# mux_geurts_3.net
KiCad netlist of a schematic drawn in EAGLE
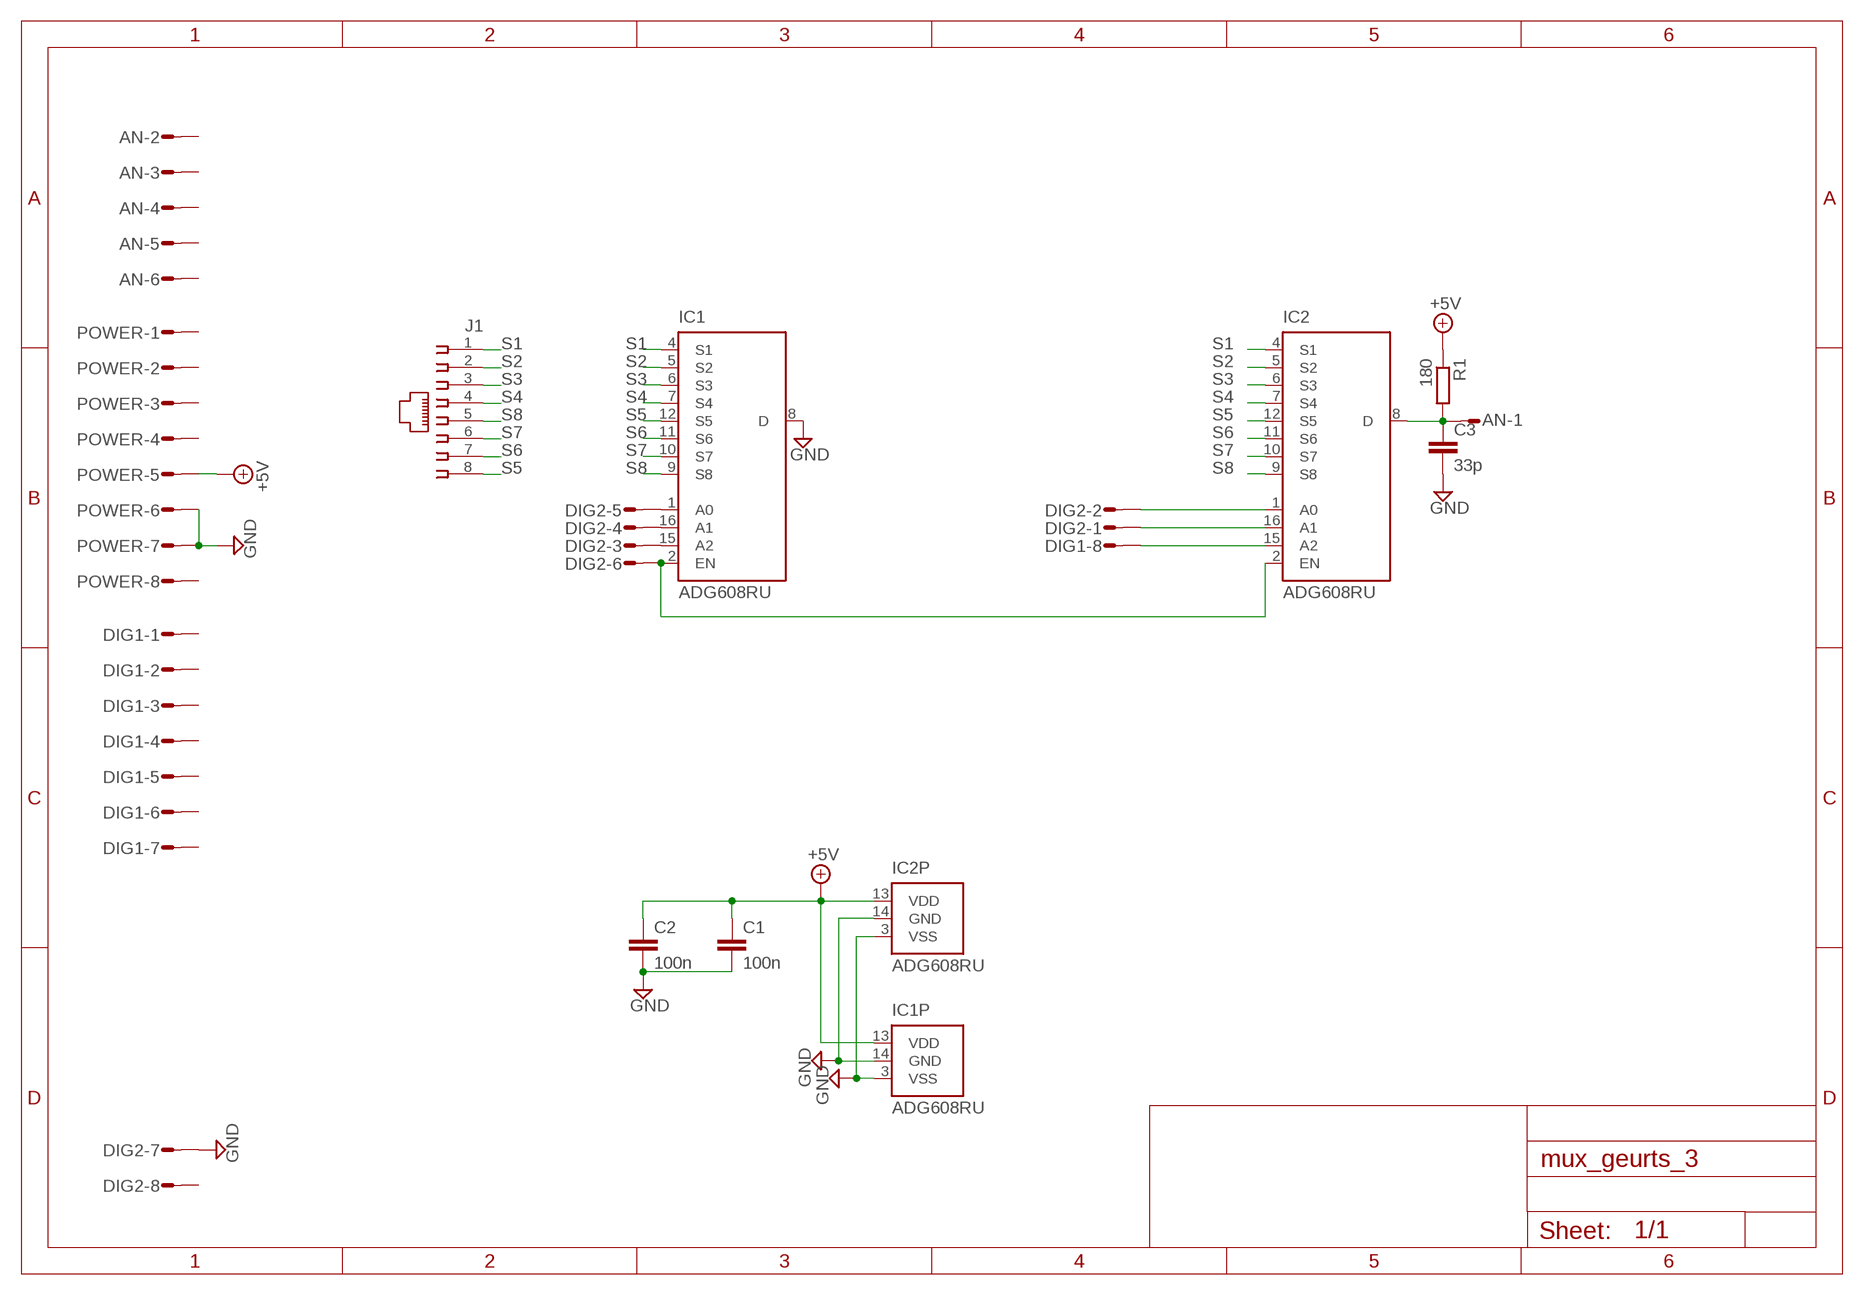
[diagram p0: schematic, sheet 1]

(export (version "E")
  (design (tool "Eeschema 10.0.6"))
  (components
    (comp (ref "AN")
      (value "M06S")
      (footprint "eagle-import:06P")
      (libsource (lib "eagle-import") (part "M06S"))
    )
    (comp (ref "C1")
      (value "100n")
      (footprint "eagle-import:C0805K")
      (libsource (lib "eagle-import") (part "C-EUC0805K"))
    )
    (comp (ref "C2")
      (value "100n")
      (footprint "eagle-import:C0805K")
      (libsource (lib "eagle-import") (part "C-EUC0805K"))
    )
    (comp (ref "C3")
      (value "33p")
      (footprint "eagle-import:C0805K")
      (libsource (lib "eagle-import") (part "C-EUC0805K"))
    )
    (comp (ref "DIG1")
      (value "M08S")
      (footprint "eagle-import:08P")
      (libsource (lib "eagle-import") (part "M08S"))
    )
    (comp (ref "DIG2")
      (value "M08S")
      (footprint "eagle-import:08P")
      (libsource (lib "eagle-import") (part "M08S"))
    )
    (comp (ref "IC1")
      (value "ADG608RU")
      (footprint "eagle-import:TSSOP16")
      (fields (field (name "MF") "ALTERA CORPORATION") (field (name "MPN") "ADG608BRU"))
      (libsource (lib "eagle-import") (part "ADG608RU"))
    )
    (comp (ref "IC2")
      (value "ADG608RU")
      (footprint "eagle-import:TSSOP16")
      (fields (field (name "MF") "ALTERA CORPORATION") (field (name "MPN") "ADG608BRU"))
      (libsource (lib "eagle-import") (part "ADG608RU"))
    )
    (comp (ref "J1")
      (value "520251-4")
      (footprint "eagle-import:520251-4")
      (libsource (lib "eagle-import") (part "520251-4"))
    )
    (comp (ref "POWER")
      (value "M08S")
      (footprint "eagle-import:08P")
      (libsource (lib "eagle-import") (part "M08S"))
    )
    (comp (ref "R1")
      (value "180")
      (footprint "eagle-import:R0805W")
      (libsource (lib "eagle-import") (part "R-EU_R0805W"))
    )
  )
  (nets
    (net (code "1") (name "+5V") (class "Default")
      (node (ref "C1") (pin "1") (pinfunction "1_1") (pintype "passive"))
      (node (ref "C2") (pin "1") (pinfunction "1_1") (pintype "passive"))
      (node (ref "IC1") (pin "13") (pinfunction "VDD_13") (pintype "power_in"))
      (node (ref "IC2") (pin "13") (pinfunction "VDD_13") (pintype "power_in"))
      (node (ref "POWER") (pin "5") (pinfunction "S_5") (pintype "passive"))
      (node (ref "R1") (pin "1") (pinfunction "1_1") (pintype "passive"))
    )
    (net (code "2") (name "/S1") (class "Default")
      (node (ref "IC1") (pin "4") (pinfunction "S1_4") (pintype "bidirectional"))
      (node (ref "IC2") (pin "4") (pinfunction "S1_4") (pintype "bidirectional"))
      (node (ref "J1") (pin "1") (pinfunction "1_1") (pintype "passive"))
    )
    (net (code "3") (name "/S2") (class "Default")
      (node (ref "IC1") (pin "5") (pinfunction "S2_5") (pintype "bidirectional"))
      (node (ref "IC2") (pin "5") (pinfunction "S2_5") (pintype "bidirectional"))
      (node (ref "J1") (pin "2") (pinfunction "2_2") (pintype "passive"))
    )
    (net (code "4") (name "/S3") (class "Default")
      (node (ref "IC1") (pin "6") (pinfunction "S3_6") (pintype "bidirectional"))
      (node (ref "IC2") (pin "6") (pinfunction "S3_6") (pintype "bidirectional"))
      (node (ref "J1") (pin "3") (pinfunction "3_3") (pintype "passive"))
    )
    (net (code "5") (name "/S4") (class "Default")
      (node (ref "IC1") (pin "7") (pinfunction "S4_7") (pintype "bidirectional"))
      (node (ref "IC2") (pin "7") (pinfunction "S4_7") (pintype "bidirectional"))
      (node (ref "J1") (pin "4") (pinfunction "4_4") (pintype "passive"))
    )
    (net (code "6") (name "/S5") (class "Default")
      (node (ref "IC1") (pin "12") (pinfunction "S5_12") (pintype "bidirectional"))
      (node (ref "IC2") (pin "12") (pinfunction "S5_12") (pintype "bidirectional"))
      (node (ref "J1") (pin "8") (pinfunction "8_8") (pintype "passive"))
    )
    (net (code "7") (name "/S6") (class "Default")
      (node (ref "IC1") (pin "11") (pinfunction "S6_11") (pintype "bidirectional"))
      (node (ref "IC2") (pin "11") (pinfunction "S6_11") (pintype "bidirectional"))
      (node (ref "J1") (pin "7") (pinfunction "7_7") (pintype "passive"))
    )
    (net (code "8") (name "/S7") (class "Default")
      (node (ref "IC1") (pin "10") (pinfunction "S7_10") (pintype "bidirectional"))
      (node (ref "IC2") (pin "10") (pinfunction "S7_10") (pintype "bidirectional"))
      (node (ref "J1") (pin "6") (pinfunction "6_6") (pintype "passive"))
    )
    (net (code "9") (name "/S8") (class "Default")
      (node (ref "IC1") (pin "9") (pinfunction "S8_9") (pintype "bidirectional"))
      (node (ref "IC2") (pin "9") (pinfunction "S8_9") (pintype "bidirectional"))
      (node (ref "J1") (pin "5") (pinfunction "5_5") (pintype "passive"))
    )
    (net (code "10") (name "GND") (class "Default")
      (node (ref "C1") (pin "2") (pinfunction "2_2") (pintype "passive"))
      (node (ref "C2") (pin "2") (pinfunction "2_2") (pintype "passive"))
      (node (ref "C3") (pin "2") (pinfunction "2_2") (pintype "passive"))
      (node (ref "DIG2") (pin "7") (pinfunction "S_7") (pintype "passive"))
      (node (ref "IC1") (pin "14") (pinfunction "GND_14") (pintype "power_in"))
      (node (ref "IC1") (pin "3") (pinfunction "VSS_3") (pintype "power_in"))
      (node (ref "IC1") (pin "8") (pinfunction "D_8") (pintype "bidirectional"))
      (node (ref "IC2") (pin "14") (pinfunction "GND_14") (pintype "power_in"))
      (node (ref "IC2") (pin "3") (pinfunction "VSS_3") (pintype "power_in"))
      (node (ref "POWER") (pin "6") (pinfunction "S_6") (pintype "passive"))
      (node (ref "POWER") (pin "7") (pinfunction "S_7") (pintype "passive"))
    )
    (net (code "11") (name "Net-(ANA-S)") (class "Default")
      (node (ref "AN") (pin "1") (pinfunction "S_1") (pintype "passive"))
      (node (ref "C3") (pin "1") (pinfunction "1_1") (pintype "passive"))
      (node (ref "IC2") (pin "8") (pinfunction "D_8") (pintype "bidirectional"))
      (node (ref "R1") (pin "2") (pinfunction "2_2") (pintype "passive"))
    )
    (net (code "12") (name "Net-(DIG1H-S)") (class "Default")
      (node (ref "DIG1") (pin "8") (pinfunction "S_8") (pintype "passive"))
      (node (ref "IC2") (pin "15") (pinfunction "A2_15") (pintype "input"))
    )
    (net (code "13") (name "Net-(DIG2A-S)") (class "Default")
      (node (ref "DIG2") (pin "1") (pinfunction "S_1") (pintype "passive"))
      (node (ref "IC2") (pin "16") (pinfunction "A1_16") (pintype "input"))
    )
    (net (code "14") (name "Net-(DIG2B-S)") (class "Default")
      (node (ref "DIG2") (pin "2") (pinfunction "S_2") (pintype "passive"))
      (node (ref "IC2") (pin "1") (pinfunction "A0_1") (pintype "input"))
    )
    (net (code "15") (name "Net-(DIG2C-S)") (class "Default")
      (node (ref "DIG2") (pin "3") (pinfunction "S_3") (pintype "passive"))
      (node (ref "IC1") (pin "15") (pinfunction "A2_15") (pintype "input"))
    )
    (net (code "16") (name "Net-(DIG2D-S)") (class "Default")
      (node (ref "DIG2") (pin "4") (pinfunction "S_4") (pintype "passive"))
      (node (ref "IC1") (pin "16") (pinfunction "A1_16") (pintype "input"))
    )
    (net (code "17") (name "Net-(DIG2E-S)") (class "Default")
      (node (ref "DIG2") (pin "5") (pinfunction "S_5") (pintype "passive"))
      (node (ref "IC1") (pin "1") (pinfunction "A0_1") (pintype "input"))
    )
    (net (code "18") (name "Net-(DIG2F-S)") (class "Default")
      (node (ref "DIG2") (pin "6") (pinfunction "S_6") (pintype "passive"))
      (node (ref "IC1") (pin "2") (pinfunction "EN_2") (pintype "input"))
      (node (ref "IC2") (pin "2") (pinfunction "EN_2") (pintype "input"))
    )
    (net (code "19") (name "unconnected-(ANB-S-Pad2)") (class "Default")
      (node (ref "AN") (pin "2") (pinfunction "S_2") (pintype "passive"))
    )
    (net (code "20") (name "unconnected-(ANC-S-Pad3)") (class "Default")
      (node (ref "AN") (pin "3") (pinfunction "S_3") (pintype "passive"))
    )
    (net (code "21") (name "unconnected-(AND-S-Pad4)") (class "Default")
      (node (ref "AN") (pin "4") (pinfunction "S_4") (pintype "passive"))
    )
    (net (code "22") (name "unconnected-(ANE-S-Pad5)") (class "Default")
      (node (ref "AN") (pin "5") (pinfunction "S_5") (pintype "passive"))
    )
    (net (code "23") (name "unconnected-(ANF-S-Pad6)") (class "Default")
      (node (ref "AN") (pin "6") (pinfunction "S_6") (pintype "passive"))
    )
    (net (code "24") (name "unconnected-(DIG1A-S-Pad1)") (class "Default")
      (node (ref "DIG1") (pin "1") (pinfunction "S_1") (pintype "passive"))
    )
    (net (code "25") (name "unconnected-(DIG1B-S-Pad2)") (class "Default")
      (node (ref "DIG1") (pin "2") (pinfunction "S_2") (pintype "passive"))
    )
    (net (code "26") (name "unconnected-(DIG1C-S-Pad3)") (class "Default")
      (node (ref "DIG1") (pin "3") (pinfunction "S_3") (pintype "passive"))
    )
    (net (code "27") (name "unconnected-(DIG1D-S-Pad4)") (class "Default")
      (node (ref "DIG1") (pin "4") (pinfunction "S_4") (pintype "passive"))
    )
    (net (code "28") (name "unconnected-(DIG1E-S-Pad5)") (class "Default")
      (node (ref "DIG1") (pin "5") (pinfunction "S_5") (pintype "passive"))
    )
    (net (code "29") (name "unconnected-(DIG1F-S-Pad6)") (class "Default")
      (node (ref "DIG1") (pin "6") (pinfunction "S_6") (pintype "passive"))
    )
    (net (code "30") (name "unconnected-(DIG1G-S-Pad7)") (class "Default")
      (node (ref "DIG1") (pin "7") (pinfunction "S_7") (pintype "passive"))
    )
    (net (code "31") (name "unconnected-(DIG2H-S-Pad8)") (class "Default")
      (node (ref "DIG2") (pin "8") (pinfunction "S_8") (pintype "passive"))
    )
    (net (code "32") (name "unconnected-(POWERA-S-Pad1)") (class "Default")
      (node (ref "POWER") (pin "1") (pinfunction "S_1") (pintype "passive"))
    )
    (net (code "33") (name "unconnected-(POWERB-S-Pad2)") (class "Default")
      (node (ref "POWER") (pin "2") (pinfunction "S_2") (pintype "passive"))
    )
    (net (code "34") (name "unconnected-(POWERC-S-Pad3)") (class "Default")
      (node (ref "POWER") (pin "3") (pinfunction "S_3") (pintype "passive"))
    )
    (net (code "35") (name "unconnected-(POWERD-S-Pad4)") (class "Default")
      (node (ref "POWER") (pin "4") (pinfunction "S_4") (pintype "passive"))
    )
    (net (code "36") (name "unconnected-(POWERH-S-Pad8)") (class "Default")
      (node (ref "POWER") (pin "8") (pinfunction "S_8") (pintype "passive"))
    )
  )
)
